# HexJacks.net
KiCad netlist of a schematic drawn in EAGLE
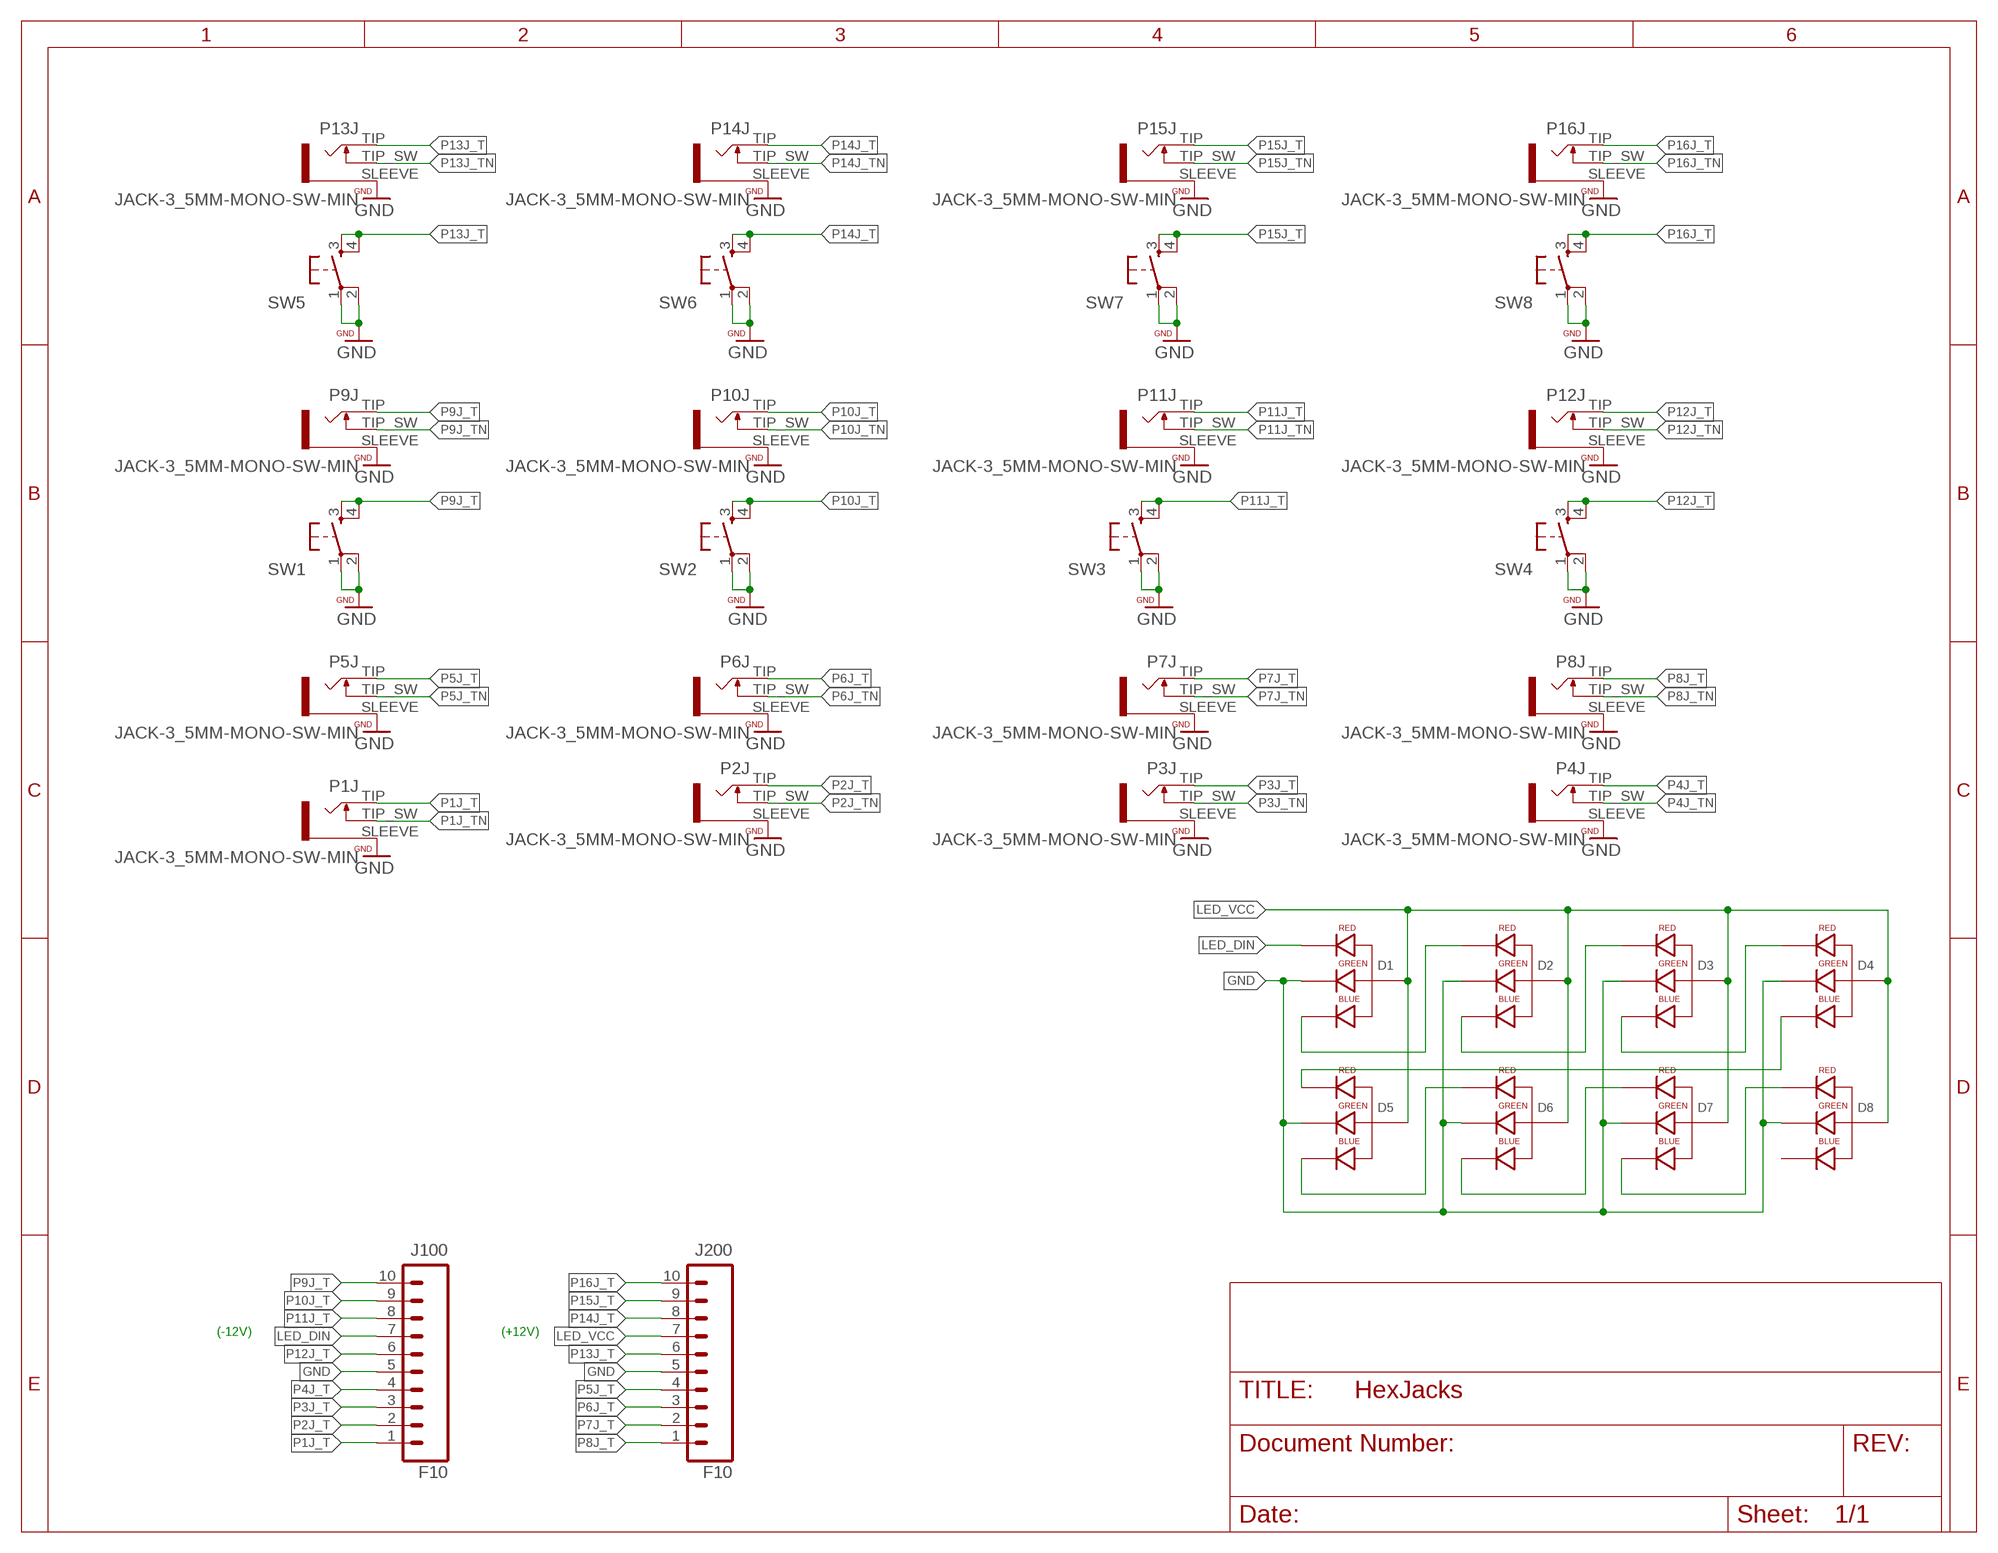
[diagram p0: schematic, sheet 1]

(export (version "E")
  (design (tool "Eeschema 10.0.6"))
  (components
    (comp (ref "D1")
      (value "LED-RGB-CA-THRUCLEAR")
      (footprint "eagle-import:LED-RGB-THRU")
      (libsource (lib "eagle-import") (part "LED-RGB-CA-THRUCLEAR"))
    )
    (comp (ref "D2")
      (value "LED-RGB-CA-THRUCLEAR")
      (footprint "eagle-import:LED-RGB-THRU")
      (libsource (lib "eagle-import") (part "LED-RGB-CA-THRUCLEAR"))
    )
    (comp (ref "D3")
      (value "LED-RGB-CA-THRUCLEAR")
      (footprint "eagle-import:LED-RGB-THRU")
      (libsource (lib "eagle-import") (part "LED-RGB-CA-THRUCLEAR"))
    )
    (comp (ref "D4")
      (value "LED-RGB-CA-THRUCLEAR")
      (footprint "eagle-import:LED-RGB-THRU")
      (libsource (lib "eagle-import") (part "LED-RGB-CA-THRUCLEAR"))
    )
    (comp (ref "D5")
      (value "LED-RGB-CA-THRUCLEAR")
      (footprint "eagle-import:LED-RGB-THRU")
      (libsource (lib "eagle-import") (part "LED-RGB-CA-THRUCLEAR"))
    )
    (comp (ref "D6")
      (value "LED-RGB-CA-THRUCLEAR")
      (footprint "eagle-import:LED-RGB-THRU")
      (libsource (lib "eagle-import") (part "LED-RGB-CA-THRUCLEAR"))
    )
    (comp (ref "D7")
      (value "LED-RGB-CA-THRUCLEAR")
      (footprint "eagle-import:LED-RGB-THRU")
      (libsource (lib "eagle-import") (part "LED-RGB-CA-THRUCLEAR"))
    )
    (comp (ref "D8")
      (value "LED-RGB-CA-THRUCLEAR")
      (footprint "eagle-import:LED-RGB-THRU")
      (libsource (lib "eagle-import") (part "LED-RGB-CA-THRUCLEAR"))
    )
    (comp (ref "J100")
      (value "F10")
      (footprint "eagle-import:1X10_OCTO")
      (libsource (lib "eagle-import") (part "M10SILK_FEMALE_PTH"))
    )
    (comp (ref "J200")
      (value "F10")
      (footprint "eagle-import:1X10_OCTO")
      (libsource (lib "eagle-import") (part "M10SILK_FEMALE_PTH"))
    )
    (comp (ref "P1J")
      (value "JACK-3_5MM-MONO-SW-MIN")
      (footprint "eagle-import:WQP_PJ301M-MIN")
      (libsource (lib "eagle-import") (part "JACK-3_5MM-MONO-SW-MIN"))
    )
    (comp (ref "P2J")
      (value "JACK-3_5MM-MONO-SW-MIN")
      (footprint "eagle-import:WQP_PJ301M-MIN")
      (libsource (lib "eagle-import") (part "JACK-3_5MM-MONO-SW-MIN"))
    )
    (comp (ref "P3J")
      (value "JACK-3_5MM-MONO-SW-MIN")
      (footprint "eagle-import:WQP_PJ301M-MIN")
      (libsource (lib "eagle-import") (part "JACK-3_5MM-MONO-SW-MIN"))
    )
    (comp (ref "P4J")
      (value "JACK-3_5MM-MONO-SW-MIN")
      (footprint "eagle-import:WQP_PJ301M-MIN")
      (libsource (lib "eagle-import") (part "JACK-3_5MM-MONO-SW-MIN"))
    )
    (comp (ref "P5J")
      (value "JACK-3_5MM-MONO-SW-MIN")
      (footprint "eagle-import:WQP_PJ301M-MIN")
      (libsource (lib "eagle-import") (part "JACK-3_5MM-MONO-SW-MIN"))
    )
    (comp (ref "P6J")
      (value "JACK-3_5MM-MONO-SW-MIN")
      (footprint "eagle-import:WQP_PJ301M-MIN")
      (libsource (lib "eagle-import") (part "JACK-3_5MM-MONO-SW-MIN"))
    )
    (comp (ref "P7J")
      (value "JACK-3_5MM-MONO-SW-MIN")
      (footprint "eagle-import:WQP_PJ301M-MIN")
      (libsource (lib "eagle-import") (part "JACK-3_5MM-MONO-SW-MIN"))
    )
    (comp (ref "P8J")
      (value "JACK-3_5MM-MONO-SW-MIN")
      (footprint "eagle-import:WQP_PJ301M-MIN")
      (libsource (lib "eagle-import") (part "JACK-3_5MM-MONO-SW-MIN"))
    )
    (comp (ref "P9J")
      (value "JACK-3_5MM-MONO-SW-MIN")
      (footprint "eagle-import:WQP_PJ301M-MIN")
      (libsource (lib "eagle-import") (part "JACK-3_5MM-MONO-SW-MIN"))
    )
    (comp (ref "P10J")
      (value "JACK-3_5MM-MONO-SW-MIN")
      (footprint "eagle-import:WQP_PJ301M-MIN")
      (libsource (lib "eagle-import") (part "JACK-3_5MM-MONO-SW-MIN"))
    )
    (comp (ref "P11J")
      (value "JACK-3_5MM-MONO-SW-MIN")
      (footprint "eagle-import:WQP_PJ301M-MIN")
      (libsource (lib "eagle-import") (part "JACK-3_5MM-MONO-SW-MIN"))
    )
    (comp (ref "P12J")
      (value "JACK-3_5MM-MONO-SW-MIN")
      (footprint "eagle-import:WQP_PJ301M-MIN")
      (libsource (lib "eagle-import") (part "JACK-3_5MM-MONO-SW-MIN"))
    )
    (comp (ref "P13J")
      (value "JACK-3_5MM-MONO-SW-MIN")
      (footprint "eagle-import:WQP_PJ301M-MIN")
      (libsource (lib "eagle-import") (part "JACK-3_5MM-MONO-SW-MIN"))
    )
    (comp (ref "P14J")
      (value "JACK-3_5MM-MONO-SW-MIN")
      (footprint "eagle-import:WQP_PJ301M-MIN")
      (libsource (lib "eagle-import") (part "JACK-3_5MM-MONO-SW-MIN"))
    )
    (comp (ref "P15J")
      (value "JACK-3_5MM-MONO-SW-MIN")
      (footprint "eagle-import:WQP_PJ301M-MIN")
      (libsource (lib "eagle-import") (part "JACK-3_5MM-MONO-SW-MIN"))
    )
    (comp (ref "P16J")
      (value "JACK-3_5MM-MONO-SW-MIN")
      (footprint "eagle-import:WQP_PJ301M-MIN")
      (libsource (lib "eagle-import") (part "JACK-3_5MM-MONO-SW-MIN"))
    )
    (comp (ref "SW1")
      (value "TAC_SWITCHPTH")
      (footprint "eagle-import:TACTILE-PTH")
      (libsource (lib "eagle-import") (part "TAC_SWITCHPTH"))
    )
    (comp (ref "SW2")
      (value "TAC_SWITCHPTH")
      (footprint "eagle-import:TACTILE-PTH")
      (libsource (lib "eagle-import") (part "TAC_SWITCHPTH"))
    )
    (comp (ref "SW3")
      (value "TAC_SWITCHPTH")
      (footprint "eagle-import:TACTILE-PTH")
      (libsource (lib "eagle-import") (part "TAC_SWITCHPTH"))
    )
    (comp (ref "SW4")
      (value "TAC_SWITCHPTH")
      (footprint "eagle-import:TACTILE-PTH")
      (libsource (lib "eagle-import") (part "TAC_SWITCHPTH"))
    )
    (comp (ref "SW5")
      (value "TAC_SWITCHPTH")
      (footprint "eagle-import:TACTILE-PTH")
      (libsource (lib "eagle-import") (part "TAC_SWITCHPTH"))
    )
    (comp (ref "SW6")
      (value "TAC_SWITCHPTH")
      (footprint "eagle-import:TACTILE-PTH")
      (libsource (lib "eagle-import") (part "TAC_SWITCHPTH"))
    )
    (comp (ref "SW7")
      (value "TAC_SWITCHPTH")
      (footprint "eagle-import:TACTILE-PTH")
      (libsource (lib "eagle-import") (part "TAC_SWITCHPTH"))
    )
    (comp (ref "SW8")
      (value "TAC_SWITCHPTH")
      (footprint "eagle-import:TACTILE-PTH")
      (libsource (lib "eagle-import") (part "TAC_SWITCHPTH"))
    )
  )
  (nets
    (net (code "1") (name "GND") (class "Default")
      (node (ref "D1") (pin "3") (pinfunction "GREEN_CATHODE_3") (pintype "bidirectional"))
      (node (ref "D2") (pin "3") (pinfunction "GREEN_CATHODE_3") (pintype "bidirectional"))
      (node (ref "D3") (pin "3") (pinfunction "GREEN_CATHODE_3") (pintype "bidirectional"))
      (node (ref "D4") (pin "3") (pinfunction "GREEN_CATHODE_3") (pintype "bidirectional"))
      (node (ref "D5") (pin "3") (pinfunction "GREEN_CATHODE_3") (pintype "bidirectional"))
      (node (ref "D6") (pin "3") (pinfunction "GREEN_CATHODE_3") (pintype "bidirectional"))
      (node (ref "D7") (pin "3") (pinfunction "GREEN_CATHODE_3") (pintype "bidirectional"))
      (node (ref "D8") (pin "3") (pinfunction "GREEN_CATHODE_3") (pintype "bidirectional"))
      (node (ref "J100") (pin "5") (pinfunction "5_5") (pintype "passive"))
      (node (ref "J200") (pin "5") (pinfunction "5_5") (pintype "passive"))
      (node (ref "P10J") (pin "SLEEVE") (pinfunction "SLEEVE_SLEEVE") (pintype "passive"))
      (node (ref "P11J") (pin "SLEEVE") (pinfunction "SLEEVE_SLEEVE") (pintype "passive"))
      (node (ref "P12J") (pin "SLEEVE") (pinfunction "SLEEVE_SLEEVE") (pintype "passive"))
      (node (ref "P13J") (pin "SLEEVE") (pinfunction "SLEEVE_SLEEVE") (pintype "passive"))
      (node (ref "P14J") (pin "SLEEVE") (pinfunction "SLEEVE_SLEEVE") (pintype "passive"))
      (node (ref "P15J") (pin "SLEEVE") (pinfunction "SLEEVE_SLEEVE") (pintype "passive"))
      (node (ref "P16J") (pin "SLEEVE") (pinfunction "SLEEVE_SLEEVE") (pintype "passive"))
      (node (ref "P1J") (pin "SLEEVE") (pinfunction "SLEEVE_SLEEVE") (pintype "passive"))
      (node (ref "P2J") (pin "SLEEVE") (pinfunction "SLEEVE_SLEEVE") (pintype "passive"))
      (node (ref "P3J") (pin "SLEEVE") (pinfunction "SLEEVE_SLEEVE") (pintype "passive"))
      (node (ref "P4J") (pin "SLEEVE") (pinfunction "SLEEVE_SLEEVE") (pintype "passive"))
      (node (ref "P5J") (pin "SLEEVE") (pinfunction "SLEEVE_SLEEVE") (pintype "passive"))
      (node (ref "P6J") (pin "SLEEVE") (pinfunction "SLEEVE_SLEEVE") (pintype "passive"))
      (node (ref "P7J") (pin "SLEEVE") (pinfunction "SLEEVE_SLEEVE") (pintype "passive"))
      (node (ref "P8J") (pin "SLEEVE") (pinfunction "SLEEVE_SLEEVE") (pintype "passive"))
      (node (ref "P9J") (pin "SLEEVE") (pinfunction "SLEEVE_SLEEVE") (pintype "passive"))
      (node (ref "SW1") (pin "1") (pinfunction "1_1") (pintype "passive"))
      (node (ref "SW1") (pin "2") (pinfunction "2_2") (pintype "passive"))
      (node (ref "SW2") (pin "1") (pinfunction "1_1") (pintype "passive"))
      (node (ref "SW2") (pin "2") (pinfunction "2_2") (pintype "passive"))
      (node (ref "SW3") (pin "1") (pinfunction "1_1") (pintype "passive"))
      (node (ref "SW3") (pin "2") (pinfunction "2_2") (pintype "passive"))
      (node (ref "SW4") (pin "1") (pinfunction "1_1") (pintype "passive"))
      (node (ref "SW4") (pin "2") (pinfunction "2_2") (pintype "passive"))
      (node (ref "SW5") (pin "1") (pinfunction "1_1") (pintype "passive"))
      (node (ref "SW5") (pin "2") (pinfunction "2_2") (pintype "passive"))
      (node (ref "SW6") (pin "1") (pinfunction "1_1") (pintype "passive"))
      (node (ref "SW6") (pin "2") (pinfunction "2_2") (pintype "passive"))
      (node (ref "SW7") (pin "1") (pinfunction "1_1") (pintype "passive"))
      (node (ref "SW7") (pin "2") (pinfunction "2_2") (pintype "passive"))
      (node (ref "SW8") (pin "1") (pinfunction "1_1") (pintype "passive"))
      (node (ref "SW8") (pin "2") (pinfunction "2_2") (pintype "passive"))
    )
    (net (code "2") (name "LED_DIN") (class "Default")
      (node (ref "D1") (pin "1") (pinfunction "RED_CATHODE_1") (pintype "bidirectional"))
      (node (ref "J100") (pin "7") (pinfunction "7_7") (pintype "passive"))
    )
    (net (code "3") (name "LED_VCC") (class "Default")
      (node (ref "D1") (pin "2") (pinfunction "ANODE_2") (pintype "bidirectional"))
      (node (ref "D2") (pin "2") (pinfunction "ANODE_2") (pintype "bidirectional"))
      (node (ref "D3") (pin "2") (pinfunction "ANODE_2") (pintype "bidirectional"))
      (node (ref "D4") (pin "2") (pinfunction "ANODE_2") (pintype "bidirectional"))
      (node (ref "D5") (pin "2") (pinfunction "ANODE_2") (pintype "bidirectional"))
      (node (ref "D6") (pin "2") (pinfunction "ANODE_2") (pintype "bidirectional"))
      (node (ref "D7") (pin "2") (pinfunction "ANODE_2") (pintype "bidirectional"))
      (node (ref "D8") (pin "2") (pinfunction "ANODE_2") (pintype "bidirectional"))
      (node (ref "J200") (pin "7") (pinfunction "7_7") (pintype "passive"))
    )
    (net (code "4") (name "Net-(D1-BLUE_CATHODE)") (class "Default")
      (node (ref "D1") (pin "4") (pinfunction "BLUE_CATHODE_4") (pintype "bidirectional"))
      (node (ref "D2") (pin "1") (pinfunction "RED_CATHODE_1") (pintype "bidirectional"))
    )
    (net (code "5") (name "Net-(D2-BLUE_CATHODE)") (class "Default")
      (node (ref "D2") (pin "4") (pinfunction "BLUE_CATHODE_4") (pintype "bidirectional"))
      (node (ref "D3") (pin "1") (pinfunction "RED_CATHODE_1") (pintype "bidirectional"))
    )
    (net (code "6") (name "Net-(D3-BLUE_CATHODE)") (class "Default")
      (node (ref "D3") (pin "4") (pinfunction "BLUE_CATHODE_4") (pintype "bidirectional"))
      (node (ref "D4") (pin "1") (pinfunction "RED_CATHODE_1") (pintype "bidirectional"))
    )
    (net (code "7") (name "Net-(D4-BLUE_CATHODE)") (class "Default")
      (node (ref "D4") (pin "4") (pinfunction "BLUE_CATHODE_4") (pintype "bidirectional"))
      (node (ref "D5") (pin "1") (pinfunction "RED_CATHODE_1") (pintype "bidirectional"))
    )
    (net (code "8") (name "Net-(D5-BLUE_CATHODE)") (class "Default")
      (node (ref "D5") (pin "4") (pinfunction "BLUE_CATHODE_4") (pintype "bidirectional"))
      (node (ref "D6") (pin "1") (pinfunction "RED_CATHODE_1") (pintype "bidirectional"))
    )
    (net (code "9") (name "Net-(D6-BLUE_CATHODE)") (class "Default")
      (node (ref "D6") (pin "4") (pinfunction "BLUE_CATHODE_4") (pintype "bidirectional"))
      (node (ref "D7") (pin "1") (pinfunction "RED_CATHODE_1") (pintype "bidirectional"))
    )
    (net (code "10") (name "Net-(D7-BLUE_CATHODE)") (class "Default")
      (node (ref "D7") (pin "4") (pinfunction "BLUE_CATHODE_4") (pintype "bidirectional"))
      (node (ref "D8") (pin "1") (pinfunction "RED_CATHODE_1") (pintype "bidirectional"))
    )
    (net (code "11") (name "P1J_T") (class "Default")
      (node (ref "J100") (pin "1") (pinfunction "1_1") (pintype "passive"))
      (node (ref "P1J") (pin "TIP") (pinfunction "TIP_TIP") (pintype "passive"))
    )
    (net (code "12") (name "P1J_TN") (class "Default")
      (node (ref "P1J") (pin "TIP_SW") (pinfunction "TIP_SW_TIP_SW") (pintype "passive"))
    )
    (net (code "13") (name "P2J_T") (class "Default")
      (node (ref "J100") (pin "2") (pinfunction "2_2") (pintype "passive"))
      (node (ref "P2J") (pin "TIP") (pinfunction "TIP_TIP") (pintype "passive"))
    )
    (net (code "14") (name "P2J_TN") (class "Default")
      (node (ref "P2J") (pin "TIP_SW") (pinfunction "TIP_SW_TIP_SW") (pintype "passive"))
    )
    (net (code "15") (name "P3J_T") (class "Default")
      (node (ref "J100") (pin "3") (pinfunction "3_3") (pintype "passive"))
      (node (ref "P3J") (pin "TIP") (pinfunction "TIP_TIP") (pintype "passive"))
    )
    (net (code "16") (name "P3J_TN") (class "Default")
      (node (ref "P3J") (pin "TIP_SW") (pinfunction "TIP_SW_TIP_SW") (pintype "passive"))
    )
    (net (code "17") (name "P4J_T") (class "Default")
      (node (ref "J100") (pin "4") (pinfunction "4_4") (pintype "passive"))
      (node (ref "P4J") (pin "TIP") (pinfunction "TIP_TIP") (pintype "passive"))
    )
    (net (code "18") (name "P4J_TN") (class "Default")
      (node (ref "P4J") (pin "TIP_SW") (pinfunction "TIP_SW_TIP_SW") (pintype "passive"))
    )
    (net (code "19") (name "P5J_T") (class "Default")
      (node (ref "J200") (pin "4") (pinfunction "4_4") (pintype "passive"))
      (node (ref "P5J") (pin "TIP") (pinfunction "TIP_TIP") (pintype "passive"))
    )
    (net (code "20") (name "P5J_TN") (class "Default")
      (node (ref "P5J") (pin "TIP_SW") (pinfunction "TIP_SW_TIP_SW") (pintype "passive"))
    )
    (net (code "21") (name "P6J_T") (class "Default")
      (node (ref "J200") (pin "3") (pinfunction "3_3") (pintype "passive"))
      (node (ref "P6J") (pin "TIP") (pinfunction "TIP_TIP") (pintype "passive"))
    )
    (net (code "22") (name "P6J_TN") (class "Default")
      (node (ref "P6J") (pin "TIP_SW") (pinfunction "TIP_SW_TIP_SW") (pintype "passive"))
    )
    (net (code "23") (name "P7J_T") (class "Default")
      (node (ref "J200") (pin "2") (pinfunction "2_2") (pintype "passive"))
      (node (ref "P7J") (pin "TIP") (pinfunction "TIP_TIP") (pintype "passive"))
    )
    (net (code "24") (name "P7J_TN") (class "Default")
      (node (ref "P7J") (pin "TIP_SW") (pinfunction "TIP_SW_TIP_SW") (pintype "passive"))
    )
    (net (code "25") (name "P8J_T") (class "Default")
      (node (ref "J200") (pin "1") (pinfunction "1_1") (pintype "passive"))
      (node (ref "P8J") (pin "TIP") (pinfunction "TIP_TIP") (pintype "passive"))
    )
    (net (code "26") (name "P8J_TN") (class "Default")
      (node (ref "P8J") (pin "TIP_SW") (pinfunction "TIP_SW_TIP_SW") (pintype "passive"))
    )
    (net (code "27") (name "P9J_T") (class "Default")
      (node (ref "J100") (pin "10") (pinfunction "10_10") (pintype "passive"))
      (node (ref "P9J") (pin "TIP") (pinfunction "TIP_TIP") (pintype "passive"))
      (node (ref "SW1") (pin "3") (pinfunction "3_3") (pintype "passive"))
      (node (ref "SW1") (pin "4") (pinfunction "4_4") (pintype "passive"))
    )
    (net (code "28") (name "P9J_TN") (class "Default")
      (node (ref "P9J") (pin "TIP_SW") (pinfunction "TIP_SW_TIP_SW") (pintype "passive"))
    )
    (net (code "29") (name "P10J_T") (class "Default")
      (node (ref "J100") (pin "9") (pinfunction "9_9") (pintype "passive"))
      (node (ref "P10J") (pin "TIP") (pinfunction "TIP_TIP") (pintype "passive"))
      (node (ref "SW2") (pin "3") (pinfunction "3_3") (pintype "passive"))
      (node (ref "SW2") (pin "4") (pinfunction "4_4") (pintype "passive"))
    )
    (net (code "30") (name "P10J_TN") (class "Default")
      (node (ref "P10J") (pin "TIP_SW") (pinfunction "TIP_SW_TIP_SW") (pintype "passive"))
    )
    (net (code "31") (name "P11J_T") (class "Default")
      (node (ref "J100") (pin "8") (pinfunction "8_8") (pintype "passive"))
      (node (ref "P11J") (pin "TIP") (pinfunction "TIP_TIP") (pintype "passive"))
      (node (ref "SW3") (pin "3") (pinfunction "3_3") (pintype "passive"))
      (node (ref "SW3") (pin "4") (pinfunction "4_4") (pintype "passive"))
    )
    (net (code "32") (name "P11J_TN") (class "Default")
      (node (ref "P11J") (pin "TIP_SW") (pinfunction "TIP_SW_TIP_SW") (pintype "passive"))
    )
    (net (code "33") (name "P12J_T") (class "Default")
      (node (ref "J100") (pin "6") (pinfunction "6_6") (pintype "passive"))
      (node (ref "P12J") (pin "TIP") (pinfunction "TIP_TIP") (pintype "passive"))
      (node (ref "SW4") (pin "3") (pinfunction "3_3") (pintype "passive"))
      (node (ref "SW4") (pin "4") (pinfunction "4_4") (pintype "passive"))
    )
    (net (code "34") (name "P12J_TN") (class "Default")
      (node (ref "P12J") (pin "TIP_SW") (pinfunction "TIP_SW_TIP_SW") (pintype "passive"))
    )
    (net (code "35") (name "P13J_T") (class "Default")
      (node (ref "J200") (pin "6") (pinfunction "6_6") (pintype "passive"))
      (node (ref "P13J") (pin "TIP") (pinfunction "TIP_TIP") (pintype "passive"))
      (node (ref "SW5") (pin "3") (pinfunction "3_3") (pintype "passive"))
      (node (ref "SW5") (pin "4") (pinfunction "4_4") (pintype "passive"))
    )
    (net (code "36") (name "P13J_TN") (class "Default")
      (node (ref "P13J") (pin "TIP_SW") (pinfunction "TIP_SW_TIP_SW") (pintype "passive"))
    )
    (net (code "37") (name "P14J_T") (class "Default")
      (node (ref "J200") (pin "8") (pinfunction "8_8") (pintype "passive"))
      (node (ref "P14J") (pin "TIP") (pinfunction "TIP_TIP") (pintype "passive"))
      (node (ref "SW6") (pin "3") (pinfunction "3_3") (pintype "passive"))
      (node (ref "SW6") (pin "4") (pinfunction "4_4") (pintype "passive"))
    )
    (net (code "38") (name "P14J_TN") (class "Default")
      (node (ref "P14J") (pin "TIP_SW") (pinfunction "TIP_SW_TIP_SW") (pintype "passive"))
    )
    (net (code "39") (name "P15J_T") (class "Default")
      (node (ref "J200") (pin "9") (pinfunction "9_9") (pintype "passive"))
      (node (ref "P15J") (pin "TIP") (pinfunction "TIP_TIP") (pintype "passive"))
      (node (ref "SW7") (pin "3") (pinfunction "3_3") (pintype "passive"))
      (node (ref "SW7") (pin "4") (pinfunction "4_4") (pintype "passive"))
    )
    (net (code "40") (name "P15J_TN") (class "Default")
      (node (ref "P15J") (pin "TIP_SW") (pinfunction "TIP_SW_TIP_SW") (pintype "passive"))
    )
    (net (code "41") (name "P16J_T") (class "Default")
      (node (ref "J200") (pin "10") (pinfunction "10_10") (pintype "passive"))
      (node (ref "P16J") (pin "TIP") (pinfunction "TIP_TIP") (pintype "passive"))
      (node (ref "SW8") (pin "3") (pinfunction "3_3") (pintype "passive"))
      (node (ref "SW8") (pin "4") (pinfunction "4_4") (pintype "passive"))
    )
    (net (code "42") (name "P16J_TN") (class "Default")
      (node (ref "P16J") (pin "TIP_SW") (pinfunction "TIP_SW_TIP_SW") (pintype "passive"))
    )
    (net (code "43") (name "unconnected-(D8-BLUE_CATHODE-Pad4)") (class "Default")
      (node (ref "D8") (pin "4") (pinfunction "BLUE_CATHODE_4") (pintype "bidirectional"))
    )
  )
)
